# Carrier_Board.net
KiCad netlist of a schematic drawn in EAGLE
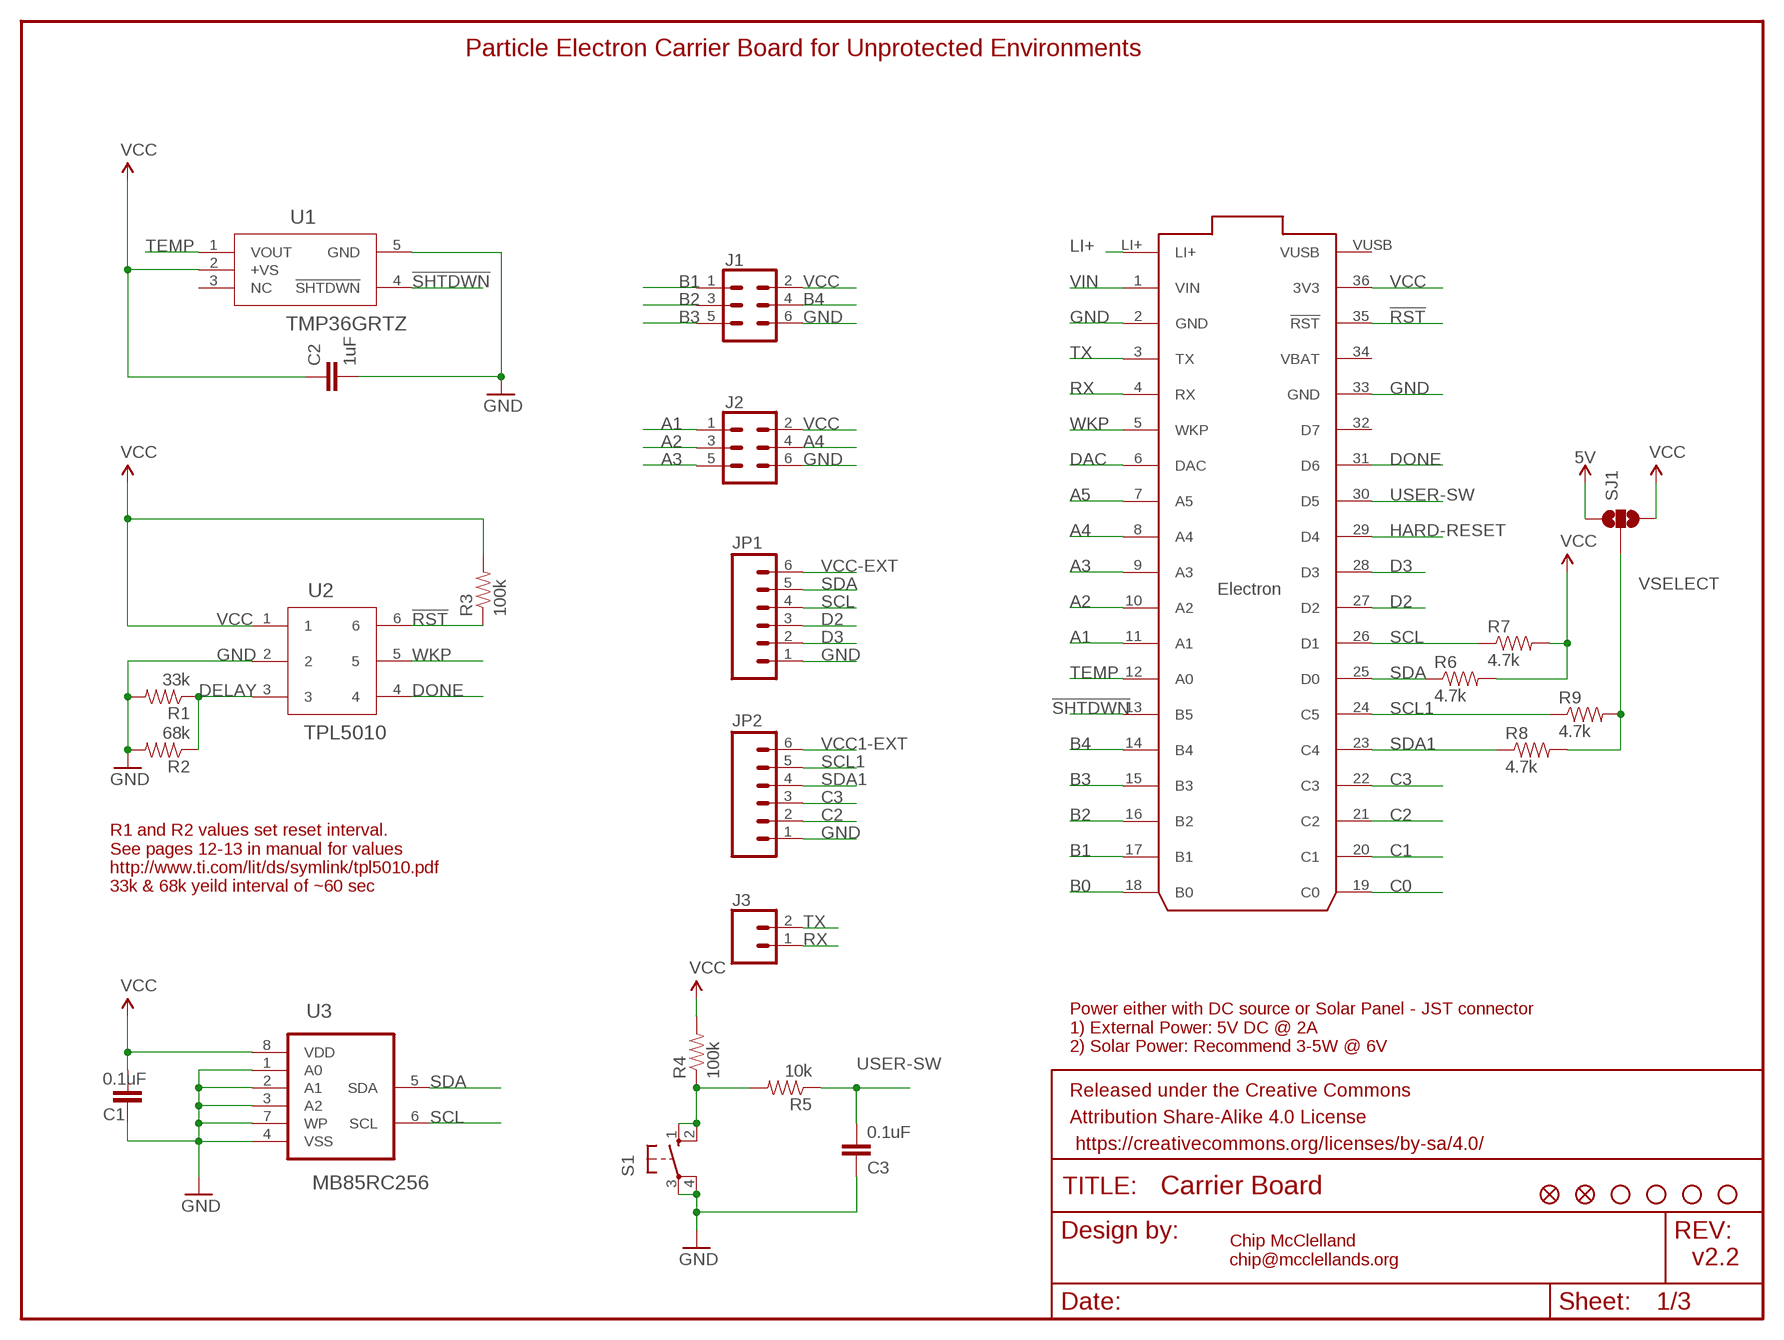
[diagram p0: schematic, sheet 1]
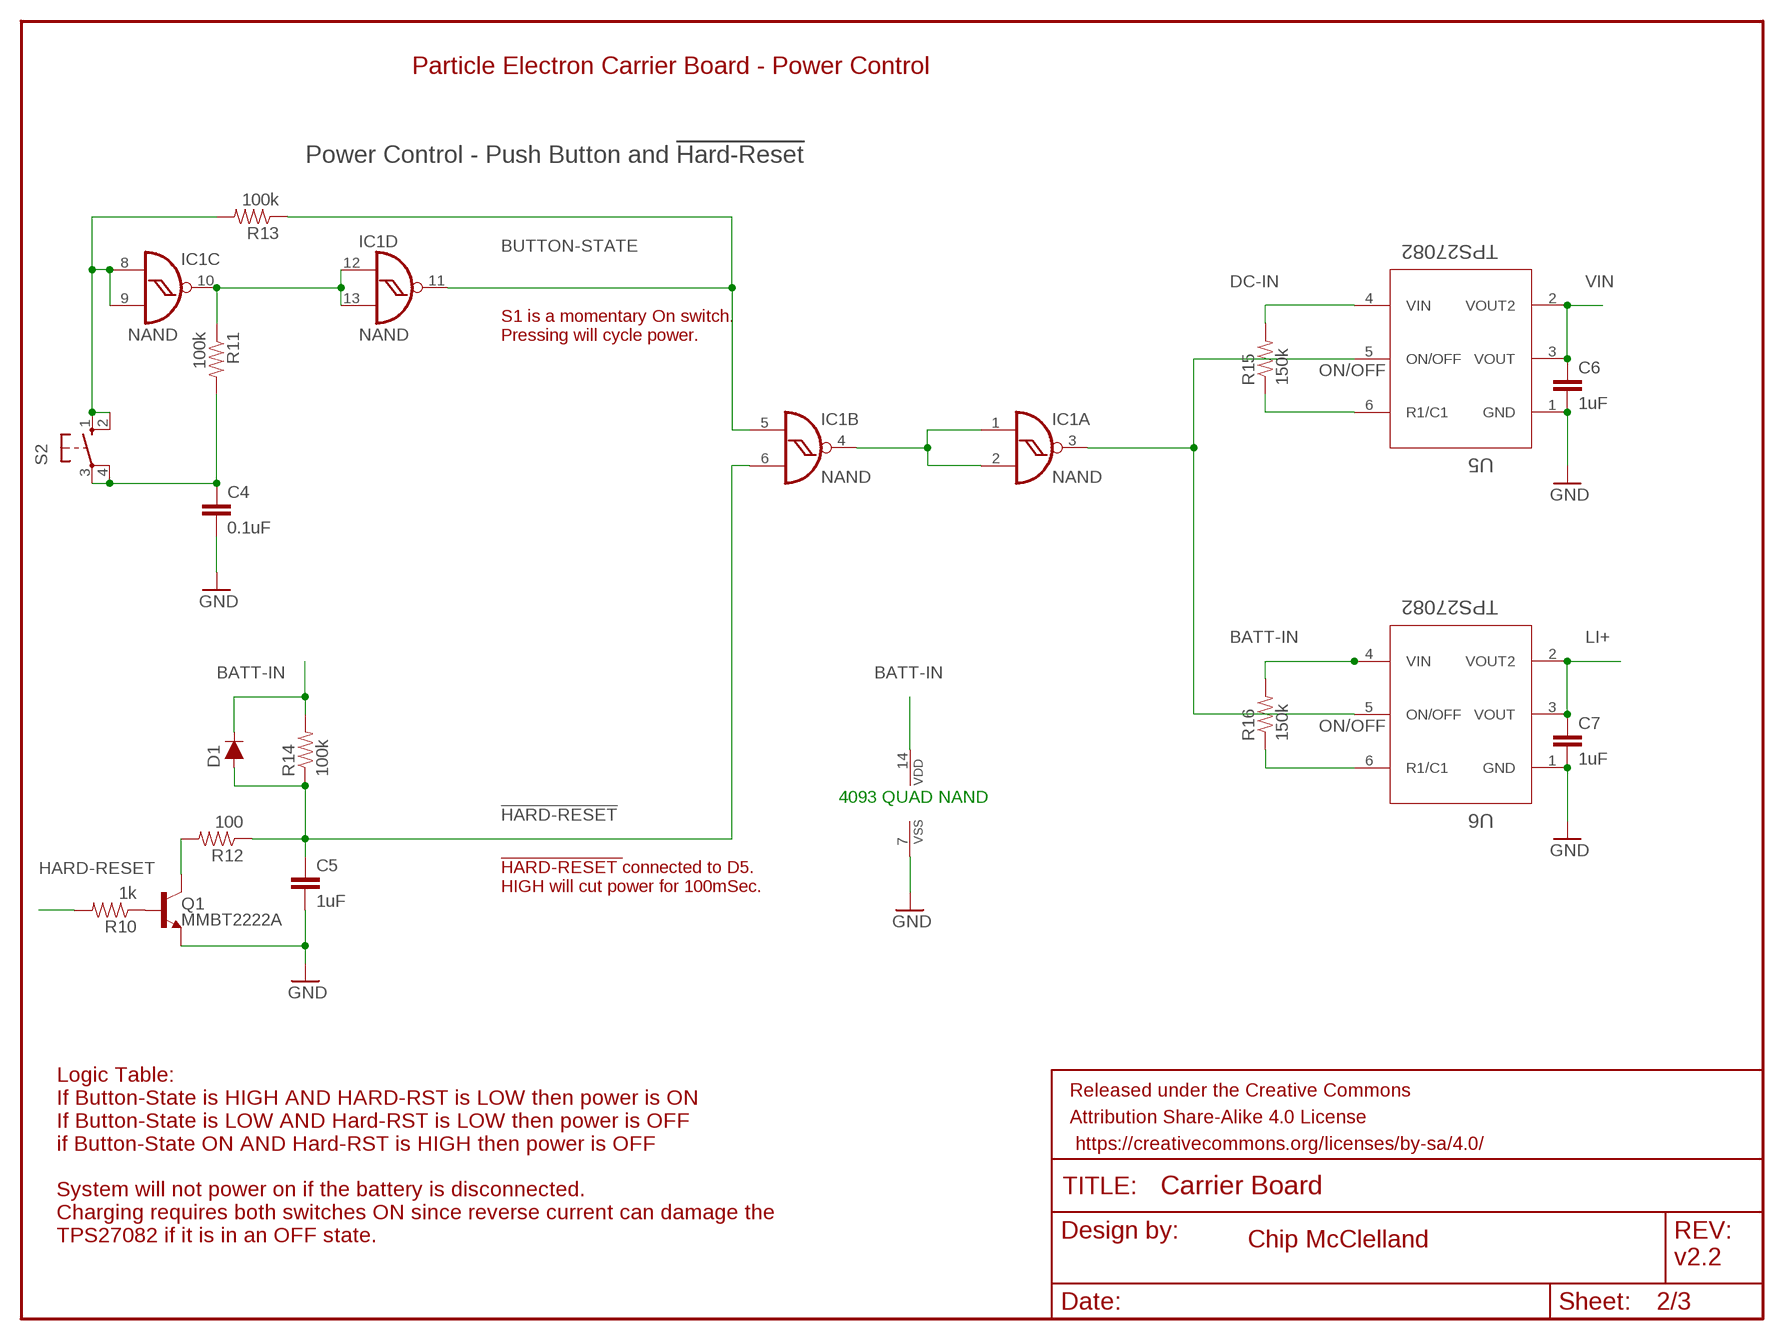
[diagram p1: schematic, sheet 2]
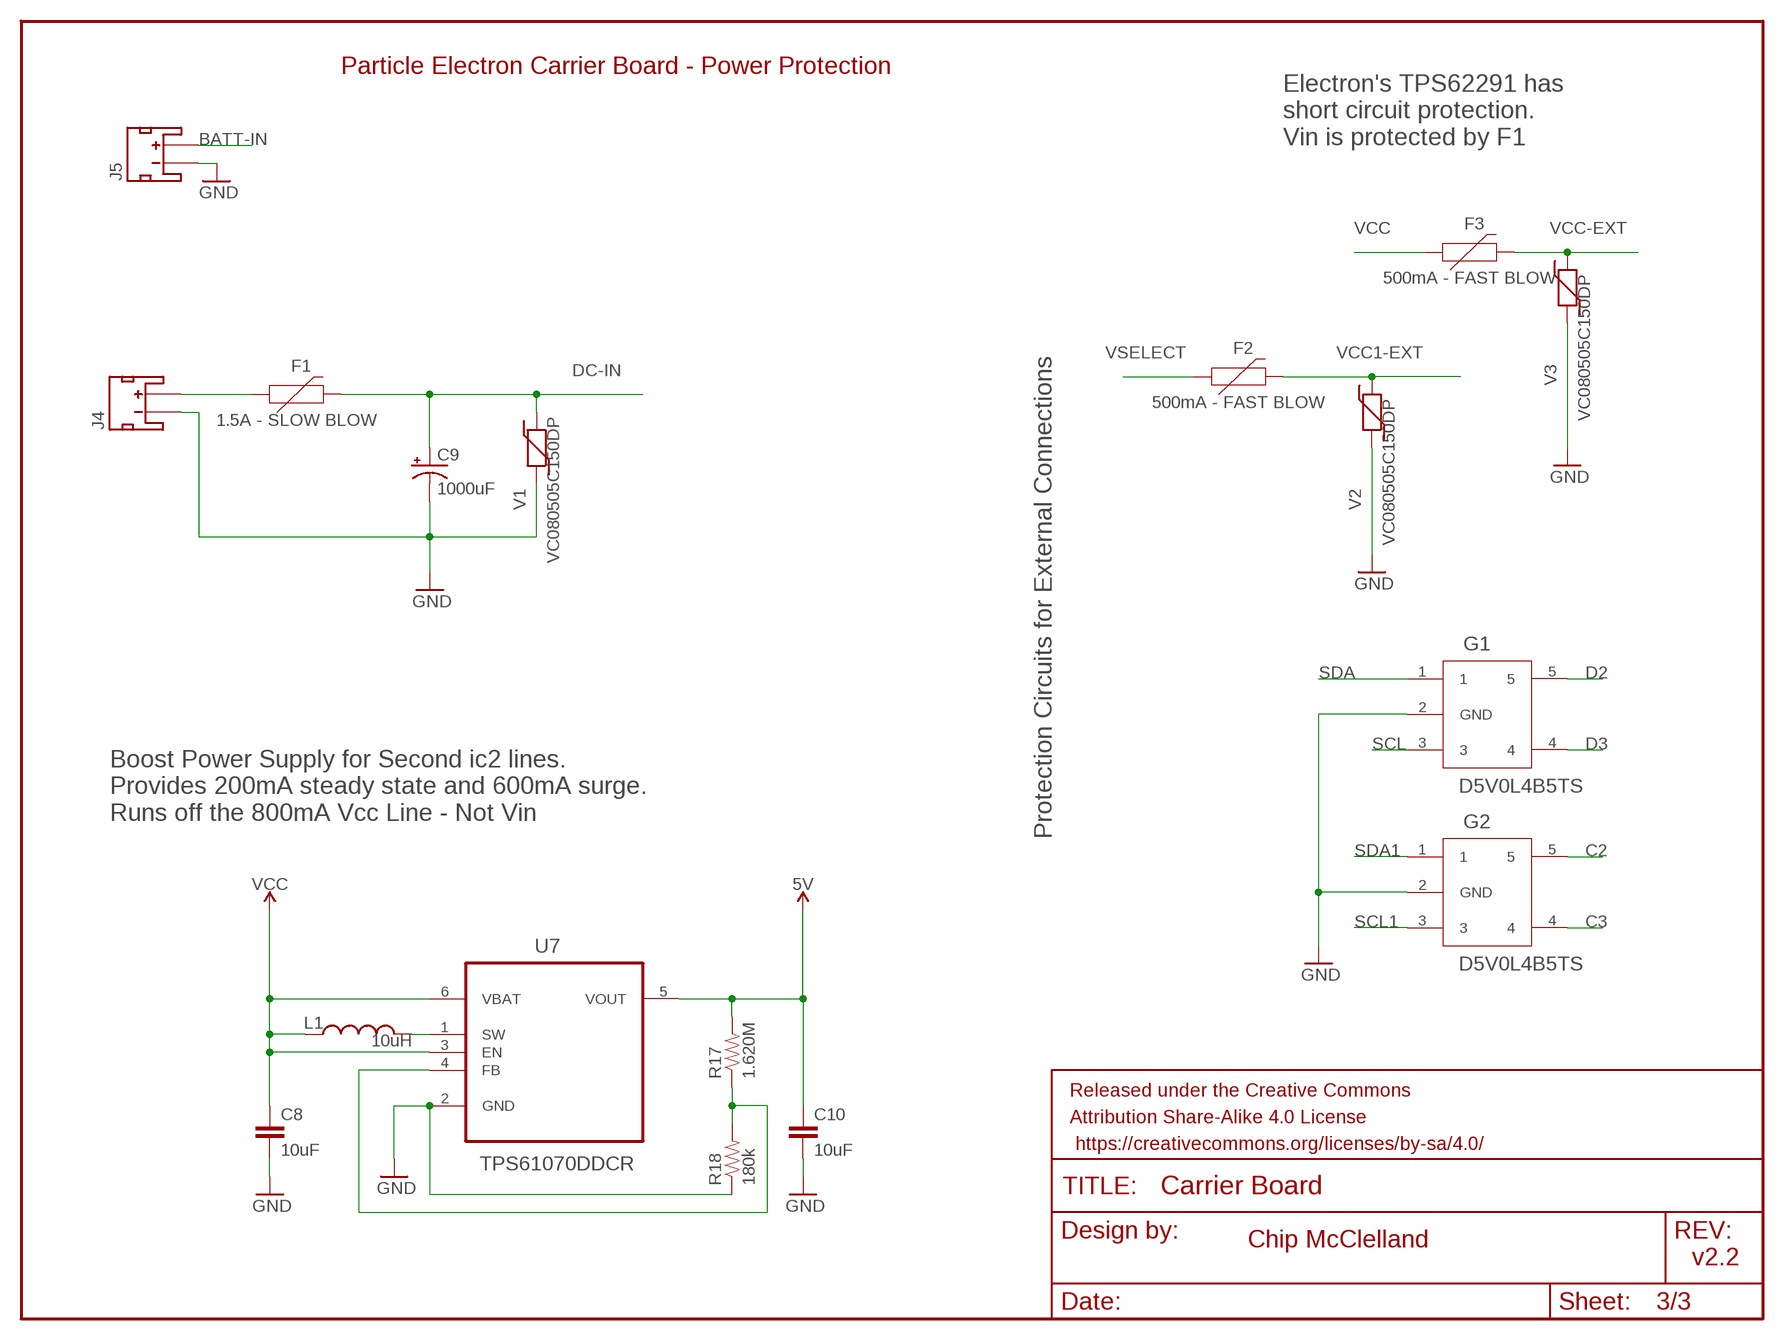
[diagram p2: schematic, sheet 3]

(export (version "E")
  (design (tool "Eeschema 10.0.6"))
  (components
    (comp (ref "C1")
      (value "0.1uF")
      (footprint "eagle-import:0805")
      (libsource (lib "eagle-import") (part "CAP0805"))
    )
    (comp (ref "C2")
      (value "1uF")
      (footprint "eagle-import:0805")
      (libsource (lib "eagle-import") (part "CAP0805"))
    )
    (comp (ref "C3")
      (value "0.1uF")
      (footprint "eagle-import:0805")
      (libsource (lib "eagle-import") (part "CAP0805"))
    )
    (comp (ref "FD1")
      (value "FIDUCIALUFIDUCIAL")
      (footprint "eagle-import:FIDUCIAL-MICRO")
      (libsource (lib "eagle-import") (part "FIDUCIALUFIDUCIAL"))
    )
    (comp (ref "FD2")
      (value "FIDUCIALUFIDUCIAL")
      (footprint "eagle-import:FIDUCIAL-MICRO")
      (libsource (lib "eagle-import") (part "FIDUCIALUFIDUCIAL"))
    )
    (comp (ref "FRAME1")
      (value "FRAME-LETTER")
      (footprint "eagle-import:CREATIVE_COMMONS")
      (libsource (lib "eagle-import") (part "FRAME-LETTER"))
    )
    (comp (ref "J1")
      (value "CONN_03X22X3_SILK_MALE_PTH")
      (footprint "eagle-import:2X3")
      (libsource (lib "eagle-import") (part "CONN_03X22X3_SILK_MALE_PTH"))
    )
    (comp (ref "J2")
      (value "CONN_03X22X3_SILK_MALE_PTH")
      (footprint "eagle-import:2X3")
      (libsource (lib "eagle-import") (part "CONN_03X22X3_SILK_MALE_PTH"))
    )
    (comp (ref "J3")
      (value "CONN_02")
      (footprint "eagle-import:1X02")
      (libsource (lib "eagle-import") (part "CONN_02"))
    )
    (comp (ref "JP1")
      (value "M06LOCK")
      (footprint "eagle-import:1X06_LOCK")
      (libsource (lib "eagle-import") (part "M06LOCK"))
    )
    (comp (ref "JP2")
      (value "M06LOCK")
      (footprint "eagle-import:1X06_LOCK")
      (libsource (lib "eagle-import") (part "M06LOCK"))
    )
    (comp (ref "JP3")
      (value "STAND-OFF")
      (footprint "eagle-import:STAND-OFF")
      (libsource (lib "eagle-import") (part "STAND-OFF"))
    )
    (comp (ref "JP4")
      (value "STAND-OFF")
      (footprint "eagle-import:STAND-OFF")
      (libsource (lib "eagle-import") (part "STAND-OFF"))
    )
    (comp (ref "JP5")
      (value "STAND-OFF")
      (footprint "eagle-import:STAND-OFF")
      (libsource (lib "eagle-import") (part "STAND-OFF"))
    )
    (comp (ref "JP6")
      (value "STAND-OFF")
      (footprint "eagle-import:STAND-OFF")
      (libsource (lib "eagle-import") (part "STAND-OFF"))
    )
    (comp (ref "R1")
      (value "33k")
      (footprint "eagle-import:0805")
      (libsource (lib "eagle-import") (part "RESISTOR0805-RES"))
    )
    (comp (ref "R2")
      (value "68k")
      (footprint "eagle-import:0805")
      (libsource (lib "eagle-import") (part "RESISTOR0805-RES"))
    )
    (comp (ref "R3")
      (value "100k")
      (footprint "eagle-import:0805")
      (libsource (lib "eagle-import") (part "RESISTOR0805-RES"))
    )
    (comp (ref "R4")
      (value "100k")
      (footprint "eagle-import:0805")
      (libsource (lib "eagle-import") (part "RESISTOR0805-RES"))
    )
    (comp (ref "R5")
      (value "10k")
      (footprint "eagle-import:0805")
      (libsource (lib "eagle-import") (part "RESISTOR0805-RES"))
    )
    (comp (ref "R6")
      (value "4.7k")
      (footprint "eagle-import:0805")
      (libsource (lib "eagle-import") (part "RESISTOR0805-RES"))
    )
    (comp (ref "R7")
      (value "4.7k")
      (footprint "eagle-import:0805")
      (libsource (lib "eagle-import") (part "RESISTOR0805-RES"))
    )
    (comp (ref "R8")
      (value "4.7k")
      (footprint "eagle-import:0805")
      (libsource (lib "eagle-import") (part "RESISTOR0805-RES"))
    )
    (comp (ref "R9")
      (value "4.7k")
      (footprint "eagle-import:0805")
      (libsource (lib "eagle-import") (part "RESISTOR0805-RES"))
    )
    (comp (ref "S1")
      (value "10-XX")
      (footprint "eagle-import:B3F-10XX")
      (libsource (lib "eagle-import") (part "10-XX"))
    )
    (comp (ref "SJ1")
      (value "SOLDERJUMPER_2WAYPASTE1&2")
      (footprint "eagle-import:SJ_3_PASTE1&2")
      (libsource (lib "eagle-import") (part "SOLDERJUMPER_2WAYPASTE1&2"))
    )
    (comp (ref "U1")
      (value "TMP36GRTZ")
      (footprint "eagle-import:RJ_5")
      (fields (field (name "MANUFACTURER_PART_NUMBER") "TMP36GRTZREEL7"))
      (libsource (lib "eagle-import") (part "TMP36GRTZ-REEL7"))
    )
    (comp (ref "U2")
      (value "TPL5010")
      (footprint "eagle-import:TSOT-23")
      (libsource (lib "eagle-import") (part "TPL5010"))
    )
    (comp (ref "U3")
      (value "MB85RC256")
      (footprint "eagle-import:SOIC127P600X175-8N")
      (fields (field (name "MPN") "MB85RC128PNF-G-JNE1"))
      (libsource (lib "eagle-import") (part "MB85RC128PNF-G-JNE1"))
    )
    (comp (ref "U4")
      (value "Particle Electron")
      (footprint "eagle-import:ELECTON-PWR-PINS")
      (libsource (lib "eagle-import") (part "ELECTRON-PWR-PINS"))
    )
    (comp (ref "C8")
      (value "10uF")
      (footprint "eagle-import:0805")
      (libsource (lib "eagle-import") (part "CAP0805"))
    )
    (comp (ref "C9")
      (value "1000uF")
      (footprint "eagle-import:PANASONIC_G")
      (libsource (lib "eagle-import") (part "CAP_POLG"))
    )
    (comp (ref "C10")
      (value "10uF")
      (footprint "eagle-import:0805")
      (libsource (lib "eagle-import") (part "CAP0805"))
    )
    (comp (ref "F1")
      (value "1.5A - SLOW BLOW")
      (footprint "eagle-import:1206")
      (libsource (lib "eagle-import") (part "PPTC_HALF-AMP"))
    )
    (comp (ref "F2")
      (value "500mA - FAST BLOW")
      (footprint "eagle-import:1206")
      (libsource (lib "eagle-import") (part "PPTC_HALF-AMP"))
    )
    (comp (ref "F3")
      (value "500mA - FAST BLOW")
      (footprint "eagle-import:1206")
      (libsource (lib "eagle-import") (part "PPTC_HALF-AMP"))
    )
    (comp (ref "FRAME3")
      (value "FRAME-LETTER")
      (footprint "eagle-import:CREATIVE_COMMONS")
      (libsource (lib "eagle-import") (part "FRAME-LETTER"))
    )
    (comp (ref "G1")
      (value "D5V0L4B5TS")
      (footprint "eagle-import:SOT-23-5")
      (libsource (lib "eagle-import") (part "D5V0L4B5TS"))
    )
    (comp (ref "G2")
      (value "D5V0L4B5TS")
      (footprint "eagle-import:SOT-23-5")
      (libsource (lib "eagle-import") (part "D5V0L4B5TS"))
    )
    (comp (ref "J4")
      (value "5V @ 2A")
      (footprint "eagle-import:JST-2-SMD")
      (libsource (lib "eagle-import") (part "JST_2MM_MALE"))
    )
    (comp (ref "J5")
      (value "JST_2MM_MALE")
      (footprint "eagle-import:JST-2-SMD")
      (libsource (lib "eagle-import") (part "JST_2MM_MALE"))
    )
    (comp (ref "L1")
      (value "10uH")
      (footprint "eagle-import:SDR0403")
      (libsource (lib "eagle-import") (part "INDUCTORSDR0403-560KL"))
    )
    (comp (ref "R17")
      (value "1.620M")
      (footprint "eagle-import:0805")
      (libsource (lib "eagle-import") (part "RESISTOR0805-RES"))
    )
    (comp (ref "R18")
      (value "180k")
      (footprint "eagle-import:0805")
      (libsource (lib "eagle-import") (part "RESISTOR0805-RES"))
    )
    (comp (ref "U7")
      (value "TPS61070DDCR")
      (footprint "eagle-import:SOT95P280X110-6N")
      (libsource (lib "eagle-import") (part "TPS61070DDCR"))
    )
    (comp (ref "V1")
      (value "VC080505C150DP")
      (footprint "eagle-import:0805")
      (libsource (lib "eagle-import") (part "VARISTOR"))
    )
    (comp (ref "V2")
      (value "VC080505C150DP")
      (footprint "eagle-import:0805")
      (libsource (lib "eagle-import") (part "VARISTOR"))
    )
    (comp (ref "V3")
      (value "VC080505C150DP")
      (footprint "eagle-import:0805")
      (libsource (lib "eagle-import") (part "VARISTOR"))
    )
    (comp (ref "C4")
      (value "0.1uF")
      (footprint "eagle-import:0805")
      (libsource (lib "eagle-import") (part "CAP0805"))
    )
    (comp (ref "C5")
      (value "1uF")
      (footprint "eagle-import:0805")
      (libsource (lib "eagle-import") (part "CAP0805"))
    )
    (comp (ref "C6")
      (value "1uF")
      (footprint "eagle-import:0805")
      (libsource (lib "eagle-import") (part "CAP0805"))
    )
    (comp (ref "C7")
      (value "1uF")
      (footprint "eagle-import:0805")
      (libsource (lib "eagle-import") (part "CAP0805"))
    )
    (comp (ref "D1")
      (value "DIODE-BAS16J")
      (footprint "eagle-import:SOD-323")
      (libsource (lib "eagle-import") (part "DIODE-BAS16J"))
    )
    (comp (ref "FRAME2")
      (value "FRAME-LETTER")
      (footprint "eagle-import:CREATIVE_COMMONS")
      (libsource (lib "eagle-import") (part "FRAME-LETTER"))
    )
    (comp (ref "IC1")
      (value "NAND")
      (footprint "eagle-import:MC14093B-TSSOP14")
      (libsource (lib "eagle-import") (part "4093DT"))
    )
    (comp (ref "Q1")
      (value "MMBT2222A")
      (footprint "eagle-import:SOT23-3")
      (libsource (lib "eagle-import") (part "TRANS_NPN-MMBT2222AL"))
    )
    (comp (ref "R10")
      (value "1k")
      (footprint "eagle-import:0805")
      (libsource (lib "eagle-import") (part "RESISTOR0805-RES"))
    )
    (comp (ref "R11")
      (value "100k")
      (footprint "eagle-import:0805")
      (libsource (lib "eagle-import") (part "RESISTOR0805-RES"))
    )
    (comp (ref "R12")
      (value "100")
      (footprint "eagle-import:0805")
      (libsource (lib "eagle-import") (part "RESISTOR0805-RES"))
    )
    (comp (ref "R13")
      (value "100k")
      (footprint "eagle-import:0805")
      (libsource (lib "eagle-import") (part "RESISTOR0805-RES"))
    )
    (comp (ref "R14")
      (value "100k")
      (footprint "eagle-import:0805")
      (libsource (lib "eagle-import") (part "RESISTOR0805-RES"))
    )
    (comp (ref "R15")
      (value "150k")
      (footprint "eagle-import:0805")
      (libsource (lib "eagle-import") (part "RESISTOR0805-RES"))
    )
    (comp (ref "R16")
      (value "150k")
      (footprint "eagle-import:0805")
      (libsource (lib "eagle-import") (part "RESISTOR0805-RES"))
    )
    (comp (ref "S2")
      (value "40-XX-ROUND")
      (footprint "eagle-import:B3F-40XX-ROUND")
      (libsource (lib "eagle-import") (part "40-XX-ROUND"))
    )
    (comp (ref "U5")
      (value "TPS27082")
      (footprint "eagle-import:TSOT-23")
      (libsource (lib "eagle-import") (part "TPS27082"))
    )
    (comp (ref "U6")
      (value "TPS27082")
      (footprint "eagle-import:TSOT-23")
      (libsource (lib "eagle-import") (part "TPS27082"))
    )
  )
  (nets
    (net (code "1") (name "5V") (class "Default")
      (node (ref "C10") (pin "1") (pinfunction "1_1") (pintype "passive"))
      (node (ref "R17") (pin "2") (pinfunction "2_2") (pintype "passive"))
      (node (ref "SJ1") (pin "1") (pinfunction "1_1") (pintype "passive"))
      (node (ref "U7") (pin "5") (pinfunction "VOUT_5") (pintype "output"))
    )
    (net (code "2") (name "A1") (class "Default")
      (node (ref "J2") (pin "1") (pinfunction "1_1") (pintype "bidirectional"))
      (node (ref "U4") (pin "11") (pinfunction "A1_11") (pintype "bidirectional"))
    )
    (net (code "3") (name "A2") (class "Default")
      (node (ref "J2") (pin "3") (pinfunction "3_3") (pintype "bidirectional"))
      (node (ref "U4") (pin "10") (pinfunction "A2_10") (pintype "bidirectional"))
    )
    (net (code "4") (name "A3") (class "Default")
      (node (ref "J2") (pin "5") (pinfunction "5_5") (pintype "bidirectional"))
      (node (ref "U4") (pin "9") (pinfunction "A3_9") (pintype "bidirectional"))
    )
    (net (code "5") (name "A4") (class "Default")
      (node (ref "J2") (pin "4") (pinfunction "4_4") (pintype "bidirectional"))
      (node (ref "U4") (pin "8") (pinfunction "A4_8") (pintype "bidirectional"))
    )
    (net (code "6") (name "A5") (class "Default")
      (node (ref "U4") (pin "7") (pinfunction "A5_7") (pintype "bidirectional"))
    )
    (net (code "7") (name "B0") (class "Default")
      (node (ref "U4") (pin "18") (pinfunction "B0_18") (pintype "bidirectional"))
    )
    (net (code "8") (name "B1") (class "Default")
      (node (ref "J1") (pin "1") (pinfunction "1_1") (pintype "bidirectional"))
      (node (ref "U4") (pin "17") (pinfunction "B1_17") (pintype "bidirectional"))
    )
    (net (code "9") (name "B2") (class "Default")
      (node (ref "J1") (pin "3") (pinfunction "3_3") (pintype "bidirectional"))
      (node (ref "U4") (pin "16") (pinfunction "B2_16") (pintype "bidirectional"))
    )
    (net (code "10") (name "B3") (class "Default")
      (node (ref "J1") (pin "5") (pinfunction "5_5") (pintype "bidirectional"))
      (node (ref "U4") (pin "15") (pinfunction "B3_15") (pintype "bidirectional"))
    )
    (net (code "11") (name "B4") (class "Default")
      (node (ref "J1") (pin "4") (pinfunction "4_4") (pintype "bidirectional"))
      (node (ref "U4") (pin "14") (pinfunction "B4_14") (pintype "bidirectional"))
    )
    (net (code "12") (name "BATT-IN") (class "Default")
      (node (ref "D1") (pin "C") (pinfunction "C_C") (pintype "passive"))
      (node (ref "IC1") (pin "14") (pinfunction "VDD_14") (pintype "power_in"))
      (node (ref "J5") (pin "2") (pinfunction "+_2") (pintype "bidirectional"))
      (node (ref "R14") (pin "2") (pinfunction "2_2") (pintype "passive"))
      (node (ref "R16") (pin "2") (pinfunction "2_2") (pintype "passive"))
      (node (ref "U6") (pin "4") (pinfunction "VIN_4") (pintype "input"))
    )
    (net (code "13") (name "BUTTON-STATE") (class "Default")
      (node (ref "IC1") (pin "11") (pinfunction "O_11") (pintype "output"))
      (node (ref "IC1") (pin "5") (pinfunction "I0_5") (pintype "input"))
      (node (ref "R13") (pin "1") (pinfunction "1_1") (pintype "passive"))
    )
    (net (code "14") (name "C0") (class "Default")
      (node (ref "U4") (pin "19") (pinfunction "C0_19") (pintype "bidirectional"))
    )
    (net (code "15") (name "C1") (class "Default")
      (node (ref "U4") (pin "20") (pinfunction "C1_20") (pintype "bidirectional"))
    )
    (net (code "16") (name "C2") (class "Default")
      (node (ref "G2") (pin "5") (pinfunction "5_5") (pintype "power_in"))
      (node (ref "JP2") (pin "2") (pinfunction "2_2") (pintype "passive"))
      (node (ref "U4") (pin "21") (pinfunction "C2_21") (pintype "bidirectional"))
    )
    (net (code "17") (name "C3") (class "Default")
      (node (ref "G2") (pin "4") (pinfunction "4_4") (pintype "input"))
      (node (ref "JP2") (pin "3") (pinfunction "3_3") (pintype "passive"))
      (node (ref "U4") (pin "22") (pinfunction "C3_22") (pintype "bidirectional"))
    )
    (net (code "18") (name "D2") (class "Default")
      (node (ref "G1") (pin "5") (pinfunction "5_5") (pintype "power_in"))
      (node (ref "JP1") (pin "3") (pinfunction "3_3") (pintype "passive"))
      (node (ref "U4") (pin "27") (pinfunction "D2_27") (pintype "bidirectional"))
    )
    (net (code "19") (name "D3") (class "Default")
      (node (ref "G1") (pin "4") (pinfunction "4_4") (pintype "input"))
      (node (ref "JP1") (pin "2") (pinfunction "2_2") (pintype "passive"))
      (node (ref "U4") (pin "28") (pinfunction "D3_28") (pintype "bidirectional"))
    )
    (net (code "20") (name "DAC") (class "Default")
      (node (ref "U4") (pin "6") (pinfunction "DAC_6") (pintype "bidirectional"))
    )
    (net (code "21") (name "DC-IN") (class "Default")
      (node (ref "C9") (pin "+") (pinfunction "+_+") (pintype "passive"))
      (node (ref "F1") (pin "2") (pinfunction "2_2") (pintype "bidirectional"))
      (node (ref "R15") (pin "2") (pinfunction "2_2") (pintype "passive"))
      (node (ref "U5") (pin "4") (pinfunction "VIN_4") (pintype "input"))
      (node (ref "V1") (pin "2") (pinfunction "2_2") (pintype "passive"))
    )
    (net (code "22") (name "DELAY") (class "Default")
      (node (ref "R1") (pin "1") (pinfunction "1_1") (pintype "passive"))
      (node (ref "R2") (pin "1") (pinfunction "1_1") (pintype "passive"))
      (node (ref "U2") (pin "3") (pinfunction "3_3") (pintype "power_in"))
    )
    (net (code "23") (name "DONE") (class "Default")
      (node (ref "U2") (pin "4") (pinfunction "4_4") (pintype "input"))
      (node (ref "U4") (pin "31") (pinfunction "D6_31") (pintype "bidirectional"))
    )
    (net (code "24") (name "GND") (class "Default")
      (node (ref "C1") (pin "2") (pinfunction "2_2") (pintype "passive"))
      (node (ref "C10") (pin "2") (pinfunction "2_2") (pintype "passive"))
      (node (ref "C2") (pin "2") (pinfunction "2_2") (pintype "passive"))
      (node (ref "C3") (pin "2") (pinfunction "2_2") (pintype "passive"))
      (node (ref "C4") (pin "2") (pinfunction "2_2") (pintype "passive"))
      (node (ref "C5") (pin "2") (pinfunction "2_2") (pintype "passive"))
      (node (ref "C6") (pin "2") (pinfunction "2_2") (pintype "passive"))
      (node (ref "C7") (pin "2") (pinfunction "2_2") (pintype "passive"))
      (node (ref "C8") (pin "2") (pinfunction "2_2") (pintype "passive"))
      (node (ref "C9") (pin "-") (pinfunction "-_-") (pintype "passive"))
      (node (ref "G1") (pin "2") (pinfunction "GND_2") (pintype "input"))
      (node (ref "G2") (pin "2") (pinfunction "GND_2") (pintype "input"))
      (node (ref "IC1") (pin "7") (pinfunction "VSS_7") (pintype "power_in"))
      (node (ref "J1") (pin "6") (pinfunction "6_6") (pintype "bidirectional"))
      (node (ref "J2") (pin "6") (pinfunction "6_6") (pintype "bidirectional"))
      (node (ref "J4") (pin "1") (pinfunction "-_1") (pintype "bidirectional"))
      (node (ref "J5") (pin "1") (pinfunction "-_1") (pintype "bidirectional"))
      (node (ref "JP1") (pin "1") (pinfunction "1_1") (pintype "passive"))
      (node (ref "JP2") (pin "1") (pinfunction "1_1") (pintype "passive"))
      (node (ref "Q1") (pin "2") (pinfunction "E_2") (pintype "passive"))
      (node (ref "R1") (pin "2") (pinfunction "2_2") (pintype "passive"))
      (node (ref "R18") (pin "1") (pinfunction "1_1") (pintype "passive"))
      (node (ref "R2") (pin "2") (pinfunction "2_2") (pintype "passive"))
      (node (ref "S1") (pin "3") (pinfunction "P_3") (pintype "passive"))
      (node (ref "S1") (pin "4") (pinfunction "P1_4") (pintype "passive"))
      (node (ref "U1") (pin "5") (pinfunction "GND_5") (pintype "passive"))
      (node (ref "U2") (pin "2") (pinfunction "2_2") (pintype "input"))
      (node (ref "U3") (pin "1") (pinfunction "A0_1") (pintype "input"))
      (node (ref "U3") (pin "2") (pinfunction "A1_2") (pintype "input"))
      (node (ref "U3") (pin "3") (pinfunction "A2_3") (pintype "input"))
      (node (ref "U3") (pin "4") (pinfunction "VSS_4") (pintype "passive"))
      (node (ref "U3") (pin "7") (pinfunction "WP_7") (pintype "input"))
      (node (ref "U4") (pin "2") (pinfunction "GND_2") (pintype "power_in"))
      (node (ref "U4") (pin "33") (pinfunction "GND_33") (pintype "power_in"))
      (node (ref "U5") (pin "1") (pinfunction "GND_1") (pintype "power_in"))
      (node (ref "U6") (pin "1") (pinfunction "GND_1") (pintype "power_in"))
      (node (ref "U7") (pin "2") (pinfunction "GND_2") (pintype "passive"))
      (node (ref "V1") (pin "1") (pinfunction "1_1") (pintype "passive"))
      (node (ref "V2") (pin "1") (pinfunction "1_1") (pintype "passive"))
      (node (ref "V3") (pin "1") (pinfunction "1_1") (pintype "passive"))
    )
    (net (code "25") (name "HARD-RESET") (class "Default")
      (node (ref "R10") (pin "2") (pinfunction "2_2") (pintype "passive"))
      (node (ref "U4") (pin "29") (pinfunction "D4_29") (pintype "bidirectional"))
    )
    (net (code "26") (name "LI+") (class "Default")
      (node (ref "C7") (pin "1") (pinfunction "1_1") (pintype "passive"))
      (node (ref "U4") (pin "LI+") (pinfunction "LI+_LI+") (pintype "bidirectional"))
      (node (ref "U6") (pin "2") (pinfunction "VOUT2_2") (pintype "power_in"))
      (node (ref "U6") (pin "3") (pinfunction "VOUT_3") (pintype "input"))
    )
    (net (code "27") (name "Net-(IC1A-I0)") (class "Default")
      (node (ref "IC1") (pin "1") (pinfunction "I0_1") (pintype "input"))
      (node (ref "IC1") (pin "2") (pinfunction "I1_2") (pintype "input"))
      (node (ref "IC1") (pin "4") (pinfunction "O_4") (pintype "output"))
    )
    (net (code "28") (name "Net-(IC1C-I0)") (class "Default")
      (node (ref "IC1") (pin "8") (pinfunction "I0_8") (pintype "input"))
      (node (ref "IC1") (pin "9") (pinfunction "I1_9") (pintype "input"))
      (node (ref "R13") (pin "2") (pinfunction "2_2") (pintype "passive"))
      (node (ref "S2") (pin "1") (pinfunction "S_1") (pintype "passive"))
      (node (ref "S2") (pin "2") (pinfunction "S1_2") (pintype "passive"))
    )
    (net (code "29") (name "Net-(IC1C-O)") (class "Default")
      (node (ref "IC1") (pin "10") (pinfunction "O_10") (pintype "output"))
      (node (ref "IC1") (pin "12") (pinfunction "I0_12") (pintype "input"))
      (node (ref "IC1") (pin "13") (pinfunction "I1_13") (pintype "input"))
      (node (ref "R11") (pin "1") (pinfunction "1_1") (pintype "passive"))
    )
    (net (code "30") (name "Net-(J4-+)") (class "Default")
      (node (ref "F1") (pin "1") (pinfunction "1_1") (pintype "bidirectional"))
      (node (ref "J4") (pin "2") (pinfunction "+_2") (pintype "bidirectional"))
    )
    (net (code "31") (name "Net-(L1-2)") (class "Default")
      (node (ref "L1") (pin "P$2") (pinfunction "2_P$2") (pintype "passive"))
      (node (ref "U7") (pin "1") (pinfunction "SW_1") (pintype "input"))
    )
    (net (code "32") (name "Net-(Q1-B)") (class "Default")
      (node (ref "Q1") (pin "1") (pinfunction "B_1") (pintype "passive"))
      (node (ref "R10") (pin "1") (pinfunction "1_1") (pintype "passive"))
    )
    (net (code "33") (name "Net-(Q1-C)") (class "Default")
      (node (ref "Q1") (pin "3") (pinfunction "C_3") (pintype "passive"))
      (node (ref "R12") (pin "2") (pinfunction "2_2") (pintype "passive"))
    )
    (net (code "34") (name "Net-(S1-S)") (class "Default")
      (node (ref "R4") (pin "1") (pinfunction "1_1") (pintype "passive"))
      (node (ref "R5") (pin "2") (pinfunction "2_2") (pintype "passive"))
      (node (ref "S1") (pin "1") (pinfunction "S_1") (pintype "passive"))
      (node (ref "S1") (pin "2") (pinfunction "S1_2") (pintype "passive"))
    )
    (net (code "35") (name "Net-(S2-P)") (class "Default")
      (node (ref "C4") (pin "1") (pinfunction "1_1") (pintype "passive"))
      (node (ref "R11") (pin "2") (pinfunction "2_2") (pintype "passive"))
      (node (ref "S2") (pin "3") (pinfunction "P_3") (pintype "passive"))
      (node (ref "S2") (pin "4") (pinfunction "P1_4") (pintype "passive"))
    )
    (net (code "36") (name "Net-(U5-R1{slash}C1)") (class "Default")
      (node (ref "R15") (pin "1") (pinfunction "1_1") (pintype "passive"))
      (node (ref "U5") (pin "6") (pinfunction "R1/C1_6") (pintype "power_in"))
    )
    (net (code "37") (name "Net-(U6-R1{slash}C1)") (class "Default")
      (node (ref "R16") (pin "1") (pinfunction "1_1") (pintype "passive"))
      (node (ref "U6") (pin "6") (pinfunction "R1/C1_6") (pintype "power_in"))
    )
    (net (code "38") (name "Net-(U7-FB)") (class "Default")
      (node (ref "R17") (pin "1") (pinfunction "1_1") (pintype "passive"))
      (node (ref "R18") (pin "2") (pinfunction "2_2") (pintype "passive"))
      (node (ref "U7") (pin "4") (pinfunction "FB_4") (pintype "input"))
    )
    (net (code "39") (name "ON{slash}OFF") (class "Default")
      (node (ref "IC1") (pin "3") (pinfunction "O_3") (pintype "output"))
      (node (ref "U5") (pin "5") (pinfunction "ON/OFF_5") (pintype "bidirectional"))
      (node (ref "U6") (pin "5") (pinfunction "ON/OFF_5") (pintype "bidirectional"))
    )
    (net (code "40") (name "RX") (class "Default")
      (node (ref "J3") (pin "1") (pinfunction "1_1") (pintype "passive"))
      (node (ref "U4") (pin "4") (pinfunction "RX_4") (pintype "bidirectional"))
    )
    (net (code "41") (name "SCL") (class "Default")
      (node (ref "G1") (pin "3") (pinfunction "3_3") (pintype "power_in"))
      (node (ref "JP1") (pin "4") (pinfunction "4_4") (pintype "passive"))
      (node (ref "R7") (pin "1") (pinfunction "1_1") (pintype "passive"))
      (node (ref "U3") (pin "6") (pinfunction "SCL_6") (pintype "input"))
      (node (ref "U4") (pin "26") (pinfunction "D1_26") (pintype "bidirectional"))
    )
    (net (code "42") (name "SCL1") (class "Default")
      (node (ref "G2") (pin "3") (pinfunction "3_3") (pintype "power_in"))
      (node (ref "JP2") (pin "5") (pinfunction "5_5") (pintype "passive"))
      (node (ref "R9") (pin "1") (pinfunction "1_1") (pintype "passive"))
      (node (ref "U4") (pin "24") (pinfunction "C5_24") (pintype "bidirectional"))
    )
    (net (code "43") (name "SDA") (class "Default")
      (node (ref "G1") (pin "1") (pinfunction "1_1") (pintype "power_in"))
      (node (ref "JP1") (pin "5") (pinfunction "5_5") (pintype "passive"))
      (node (ref "R6") (pin "1") (pinfunction "1_1") (pintype "passive"))
      (node (ref "U3") (pin "5") (pinfunction "SDA_5") (pintype "bidirectional"))
      (node (ref "U4") (pin "25") (pinfunction "D0_25") (pintype "bidirectional"))
    )
    (net (code "44") (name "SDA1") (class "Default")
      (node (ref "G2") (pin "1") (pinfunction "1_1") (pintype "power_in"))
      (node (ref "JP2") (pin "4") (pinfunction "4_4") (pintype "passive"))
      (node (ref "R8") (pin "1") (pinfunction "1_1") (pintype "passive"))
      (node (ref "U4") (pin "23") (pinfunction "C4_23") (pintype "bidirectional"))
    )
    (net (code "45") (name "TEMP") (class "Default")
      (node (ref "U1") (pin "1") (pinfunction "VOUT_1") (pintype "passive"))
      (node (ref "U4") (pin "12") (pinfunction "A0_12") (pintype "bidirectional"))
    )
    (net (code "46") (name "TX") (class "Default")
      (node (ref "J3") (pin "2") (pinfunction "2_2") (pintype "passive"))
      (node (ref "U4") (pin "3") (pinfunction "TX_3") (pintype "bidirectional"))
    )
    (net (code "47") (name "USER-SW") (class "Default")
      (node (ref "C3") (pin "1") (pinfunction "1_1") (pintype "passive"))
      (node (ref "R5") (pin "1") (pinfunction "1_1") (pintype "passive"))
      (node (ref "U4") (pin "30") (pinfunction "D5_30") (pintype "bidirectional"))
    )
    (net (code "48") (name "VBAT") (class "Default")
      (node (ref "U4") (pin "34") (pinfunction "VBAT_34") (pintype "power_in"))
    )
    (net (code "49") (name "VCC") (class "Default")
      (node (ref "C1") (pin "1") (pinfunction "1_1") (pintype "passive"))
      (node (ref "C2") (pin "1") (pinfunction "1_1") (pintype "passive"))
      (node (ref "C8") (pin "1") (pinfunction "1_1") (pintype "passive"))
      (node (ref "F3") (pin "1") (pinfunction "1_1") (pintype "bidirectional"))
      (node (ref "J1") (pin "2") (pinfunction "2_2") (pintype "bidirectional"))
      (node (ref "J2") (pin "2") (pinfunction "2_2") (pintype "bidirectional"))
      (node (ref "L1") (pin "P$1") (pinfunction "1_P$1") (pintype "passive"))
      (node (ref "R3") (pin "2") (pinfunction "2_2") (pintype "passive"))
      (node (ref "R4") (pin "2") (pinfunction "2_2") (pintype "passive"))
      (node (ref "R6") (pin "2") (pinfunction "2_2") (pintype "passive"))
      (node (ref "R7") (pin "2") (pinfunction "2_2") (pintype "passive"))
      (node (ref "SJ1") (pin "3") (pinfunction "3_3") (pintype "passive"))
      (node (ref "U1") (pin "2") (pinfunction "+VS_2") (pintype "power_in"))
      (node (ref "U2") (pin "1") (pinfunction "1_1") (pintype "power_in"))
      (node (ref "U3") (pin "8") (pinfunction "VDD_8") (pintype "power_in"))
      (node (ref "U4") (pin "36") (pinfunction "3V3_36") (pintype "power_in"))
      (node (ref "U7") (pin "3") (pinfunction "EN_3") (pintype "input"))
      (node (ref "U7") (pin "6") (pinfunction "VBAT_6") (pintype "power_in"))
    )
    (net (code "50") (name "VCC-EXT") (class "Default")
      (node (ref "F3") (pin "2") (pinfunction "2_2") (pintype "bidirectional"))
      (node (ref "JP1") (pin "6") (pinfunction "6_6") (pintype "passive"))
      (node (ref "V3") (pin "2") (pinfunction "2_2") (pintype "passive"))
    )
    (net (code "51") (name "VCC1-EXT") (class "Default")
      (node (ref "F2") (pin "2") (pinfunction "2_2") (pintype "bidirectional"))
      (node (ref "JP2") (pin "6") (pinfunction "6_6") (pintype "passive"))
      (node (ref "V2") (pin "2") (pinfunction "2_2") (pintype "passive"))
    )
    (net (code "52") (name "VIN") (class "Default")
      (node (ref "C6") (pin "1") (pinfunction "1_1") (pintype "passive"))
      (node (ref "U4") (pin "1") (pinfunction "VIN_1") (pintype "power_in"))
      (node (ref "U5") (pin "2") (pinfunction "VOUT2_2") (pintype "power_in"))
      (node (ref "U5") (pin "3") (pinfunction "VOUT_3") (pintype "input"))
    )
    (net (code "53") (name "VSELECT") (class "Default")
      (node (ref "F2") (pin "1") (pinfunction "1_1") (pintype "bidirectional"))
      (node (ref "R8") (pin "2") (pinfunction "2_2") (pintype "passive"))
      (node (ref "R9") (pin "2") (pinfunction "2_2") (pintype "passive"))
      (node (ref "SJ1") (pin "2") (pinfunction "2_2") (pintype "passive"))
    )
    (net (code "54") (name "WKP") (class "Default")
      (node (ref "U2") (pin "5") (pinfunction "5_5") (pintype "bidirectional"))
      (node (ref "U4") (pin "5") (pinfunction "WKP_5") (pintype "bidirectional"))
    )
    (net (code "55") (name "unconnected-(J4-PAD1-PadNC1)") (class "Default")
      (node (ref "J4") (pin "NC1") (pinfunction "PAD1_NC1") (pintype "bidirectional"))
    )
    (net (code "56") (name "unconnected-(J4-PAD2-PadNC2)") (class "Default")
      (node (ref "J4") (pin "NC2") (pinfunction "PAD2_NC2") (pintype "bidirectional"))
    )
    (net (code "57") (name "unconnected-(J5-PAD1-PadNC1)") (class "Default")
      (node (ref "J5") (pin "NC1") (pinfunction "PAD1_NC1") (pintype "bidirectional"))
    )
    (net (code "58") (name "unconnected-(J5-PAD2-PadNC2)") (class "Default")
      (node (ref "J5") (pin "NC2") (pinfunction "PAD2_NC2") (pintype "bidirectional"))
    )
    (net (code "59") (name "unconnected-(U1-NC-Pad3)") (class "Default")
      (node (ref "U1") (pin "3") (pinfunction "NC_3") (pintype "passive"))
    )
    (net (code "60") (name "unconnected-(U4-D7-Pad32)") (class "Default")
      (node (ref "U4") (pin "32") (pinfunction "D7_32") (pintype "bidirectional"))
    )
    (net (code "61") (name "unconnected-(U4-PadVUSB)") (class "Default")
      (node (ref "U4") (pin "VUSB") (pinfunction "VUSB_VUSB") (pintype "bidirectional"))
    )
    (net (code "62") (name "~{HARD-RESET}") (class "Default")
      (node (ref "C5") (pin "1") (pinfunction "1_1") (pintype "passive"))
      (node (ref "D1") (pin "A") (pinfunction "A_A") (pintype "passive"))
      (node (ref "IC1") (pin "6") (pinfunction "I1_6") (pintype "input"))
      (node (ref "R12") (pin "1") (pinfunction "1_1") (pintype "passive"))
      (node (ref "R14") (pin "1") (pinfunction "1_1") (pintype "passive"))
    )
    (net (code "63") (name "~{RST}") (class "Default")
      (node (ref "R3") (pin "1") (pinfunction "1_1") (pintype "passive"))
      (node (ref "U2") (pin "6") (pinfunction "6_6") (pintype "power_in"))
      (node (ref "U4") (pin "35") (pinfunction "~{RST}_35") (pintype "bidirectional"))
    )
    (net (code "64") (name "~{SHTDWN}") (class "Default")
      (node (ref "U1") (pin "4") (pinfunction "~{SHTDWN}_4") (pintype "passive"))
      (node (ref "U4") (pin "13") (pinfunction "B5_13") (pintype "bidirectional"))
    )
  )
)
